# power.net
KiCad netlist of a schematic drawn in Altium Designer
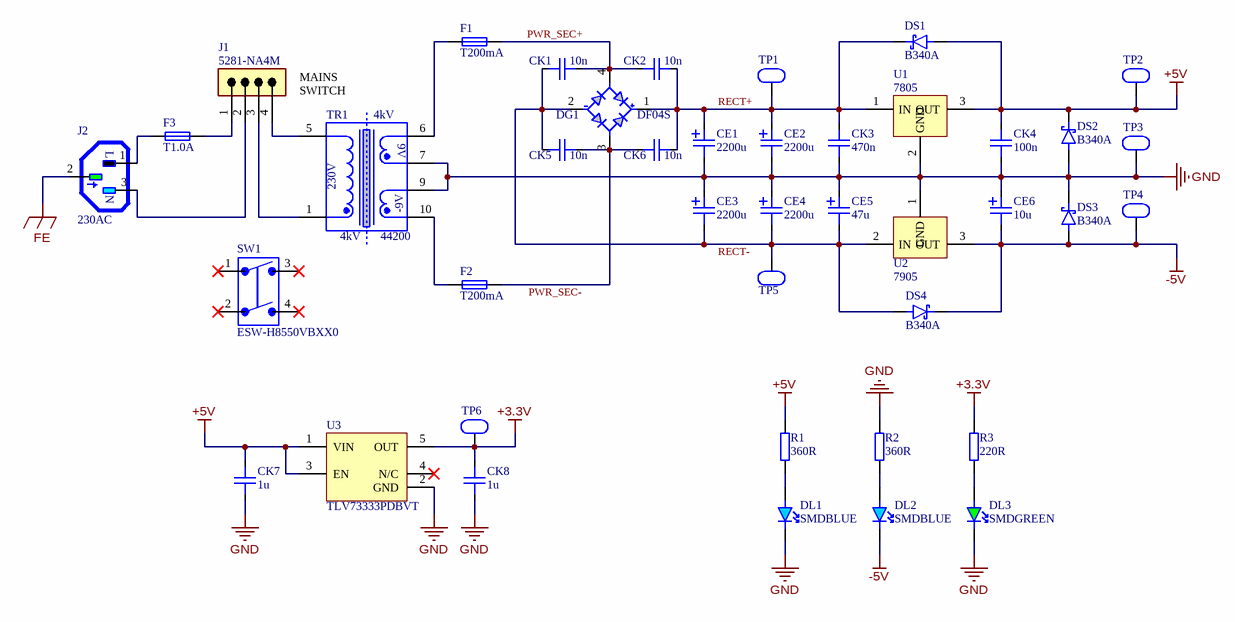
[diagram p0: power.SchDoc]

(export (version "E")
  (design (tool "Eeschema 10.0.6"))
  (components
    (comp (ref "CE1")
      (value "2200u")
      (footprint "ECE_16x31.5_RM7.5")
      (description "C; 2200u; 35V; 20%; Aluminum Electrolytic; ??;")
      (fields (field (name "MANUFACTURER") "SU'SCON: SL035M222J26SR;;SU'SCON: SL035M222J26TKKKS00R"))
      (libsource (lib "altium_sql") (part "CE"))
    )
    (comp (ref "CE2")
      (value "2200u")
      (footprint "ECE_16x31.5_RM7.5")
      (description "C; 2200u; 35V; 20%; Aluminum Electrolytic; ??;")
      (fields (field (name "MANUFACTURER") "SU'SCON: SL035M222J26SR;;SU'SCON: SL035M222J26TKKKS00R"))
      (libsource (lib "altium_sql") (part "CE"))
    )
    (comp (ref "CE3")
      (value "2200u")
      (footprint "ECE_16x31.5_RM7.5")
      (description "C; 2200u; 35V; 20%; Aluminum Electrolytic; ??;")
      (fields (field (name "MANUFACTURER") "SU'SCON: SL035M222J26SR;;SU'SCON: SL035M222J26TKKKS00R"))
      (libsource (lib "altium_sql") (part "CE"))
    )
    (comp (ref "CE4")
      (value "2200u")
      (footprint "ECE_16x31.5_RM7.5")
      (description "C; 2200u; 35V; 20%; Aluminum Electrolytic; ??;")
      (fields (field (name "MANUFACTURER") "SU'SCON: SL035M222J26SR;;SU'SCON: SL035M222J26TKKKS00R"))
      (libsource (lib "altium_sql") (part "CE"))
    )
    (comp (ref "CE5")
      (value "47u")
      (footprint "CAPAE6.8X6.8(D_SIZE)")
      (description "C; 47u; 35V; 20%; Aluminum Electrolytic; ??;")
      (fields (field (name "MANUFACTURER") "Surge, MPN: SVZ21V470M0605V1"))
      (libsource (lib "altium_sql") (part "CE"))
    )
    (comp (ref "CE6")
      (value "10u")
      (footprint "CAPAE5.5X5.5(C_SIZE)")
      (description "C; 10u; 35V; 20%; Aluminum Electrolytic; ??;")
      (fields (field (name "MANUFACTURER") "SAMWHA: SC1V106M05005VR259;;SAMWHA: SC1V106M05005VR289"))
      (libsource (lib "altium_sql") (part "CE"))
    )
    (comp (ref "CK1")
      (value "10n")
      (footprint "CAPC1608X09N(SMC0603)")
      (description "C; 10n; 50V; 5%; NP0/C0G; ??;")
      (fields (field (name "MANUFACTURER") "TDK: C1608C0G1H103J080AA"))
      (libsource (lib "altium_sql") (part "CK"))
    )
    (comp (ref "CK2")
      (value "10n")
      (footprint "CAPC1608X09N(SMC0603)")
      (description "C; 10n; 50V; 5%; NP0/C0G; ??;")
      (fields (field (name "MANUFACTURER") "TDK: C1608C0G1H103J080AA"))
      (libsource (lib "altium_sql") (part "CK"))
    )
    (comp (ref "CK3")
      (value "470n")
      (footprint "CAPC1608X09N(SMC0603)")
      (description "C; 470n; 50V; 10%; X7R; ??;")
      (fields
        (field (name "MANUFACTURER") "TDK: C1608X7R1H474KT-S;;TDK: C1608X7R1H474KT000E;;TDK: C1608X7R1H474K080AC")
      )
      (libsource (lib "altium_sql") (part "CK"))
    )
    (comp (ref "CK4")
      (value "100n")
      (footprint "CAPC1608X09N(SMC0603)")
      (description "C; 100n; 100V; 10%; X7R; ??;")
      (fields
        (field (name "MANUFACTURER") "Murata Electronics: GRM188R72A104KA35D;;Yageo: CC0603KRX7R0BB104")
      )
      (libsource (lib "altium_sql") (part "CK"))
    )
    (comp (ref "CK5")
      (value "10n")
      (footprint "CAPC1608X09N(SMC0603)")
      (description "C; 10n; 50V; 5%; NP0/C0G; ??;")
      (fields (field (name "MANUFACTURER") "TDK: C1608C0G1H103J080AA"))
      (libsource (lib "altium_sql") (part "CK"))
    )
    (comp (ref "CK6")
      (value "10n")
      (footprint "CAPC1608X09N(SMC0603)")
      (description "C; 10n; 50V; 5%; NP0/C0G; ??;")
      (fields (field (name "MANUFACTURER") "TDK: C1608C0G1H103J080AA"))
      (libsource (lib "altium_sql") (part "CK"))
    )
    (comp (ref "CK7")
      (value "1u")
      (footprint "CAPC1608X09N(SMC0603)")
      (description "C; 1u; 50V; 10%; X5R; ??;")
      (libsource (lib "altium_sql") (part "CK"))
    )
    (comp (ref "CK8")
      (value "1u")
      (footprint "CAPC1608X09N(SMC0603)")
      (description "C; 1u; 50V; 10%; X5R; ??;")
      (libsource (lib "altium_sql") (part "CK"))
    )
    (comp (ref "DG1")
      (value "DF04S")
      (footprint "DIP300RM5.08_SMD")
      (description "D; Bridge; 400V; 1A; 1x;")
      (libsource (lib "altium_sql") (part "EDG+DF04SXX0"))
    )
    (comp (ref "DL1")
      (value "SMDBLUE")
      (footprint "DIOC2012X12N(SMLED0805)B")
      (description "Ind; Light; Blue;")
      (fields (field (name "MANUFACTURER") "MULTICOMP: OVS-0803"))
      (libsource (lib "altium_sql") (part "DL_B"))
    )
    (comp (ref "DL2")
      (value "SMDBLUE")
      (footprint "DIOC2012X12N(SMLED0805)B")
      (description "Ind; Light; Blue;")
      (fields (field (name "MANUFACTURER") "MULTICOMP: OVS-0803"))
      (libsource (lib "altium_sql") (part "DL_B"))
    )
    (comp (ref "DL3")
      (value "SMDGREEN")
      (footprint "DIOC2012X12N(SMLED0805)G")
      (description "Ind; Light; Green;")
      (fields (field (name "MANUFACTURER") "HEBEI: 0805KGCT;;BRIGHTLED: BL-HGE35A-AV-TRB"))
      (libsource (lib "altium_sql") (part "DL_G"))
    )
    (comp (ref "DS1")
      (value "B340A")
      (footprint "DIOM5127X23N(SMA)")
      (description "D; Schottky; 40V; 3A; 1x;")
      (fields
        (field (name "MANUFACTURER") "DIODES INC: B340A-13-F;;ONS: MBRA340T3G;;VISHAY: SSA34;;BOURNS: B340LF;;MCC: SK34A-LTP")
      )
      (libsource (lib "altium_sql") (part "DS"))
    )
    (comp (ref "DS2")
      (value "B340A")
      (footprint "DIOM5127X23N(SMA)")
      (description "D; Schottky; 40V; 3A; 1x;")
      (fields
        (field (name "MANUFACTURER") "DIODES INC: B340A-13-F;;ONS: MBRA340T3G;;VISHAY: SSA34;;BOURNS: B340LF;;MCC: SK34A-LTP")
      )
      (libsource (lib "altium_sql") (part "DS"))
    )
    (comp (ref "DS3")
      (value "B340A")
      (footprint "DIOM5127X23N(SMA)")
      (description "D; Schottky; 40V; 3A; 1x;")
      (fields
        (field (name "MANUFACTURER") "DIODES INC: B340A-13-F;;ONS: MBRA340T3G;;VISHAY: SSA34;;BOURNS: B340LF;;MCC: SK34A-LTP")
      )
      (libsource (lib "altium_sql") (part "DS"))
    )
    (comp (ref "DS4")
      (value "B340A")
      (footprint "DIOM5127X23N(SMA)")
      (description "D; Schottky; 40V; 3A; 1x;")
      (fields
        (field (name "MANUFACTURER") "DIODES INC: B340A-13-F;;ONS: MBRA340T3G;;VISHAY: SSA34;;BOURNS: B340LF;;MCC: SK34A-LTP")
      )
      (libsource (lib "altium_sql") (part "DS"))
    )
    (comp (ref "F1")
      (value "T200mA")
      (footprint "FUSE-C8.5")
      (description "CP; Current [A]; 0.2; R:No; 1x;")
      (fields (field (name "MANUFACTURER") "SCHURTER: MST250 0034.6608;;SCHURTER: MST250 0034.6708"))
      (libsource (lib "altium_sql") (part "FUSE_PCB"))
    )
    (comp (ref "F2")
      (value "T200mA")
      (footprint "FUSE-C8.5")
      (description "CP; Current [A]; 0.2; R:No; 1x;")
      (fields (field (name "MANUFACTURER") "SCHURTER: MST250 0034.6608;;SCHURTER: MST250 0034.6708"))
      (libsource (lib "altium_sql") (part "FUSE_PCB"))
    )
    (comp (ref "F3")
      (value "T1.0A")
      (footprint "FUSE-C8.5")
      (description "CP; Current [A]; 1; R:No; 1x;")
      (fields (field (name "MANUFACTURER") "SCHURTER: 34,6615"))
      (libsource (lib "altium_sql") (part "FUSE_PCB"))
    )
    (comp (ref "J1")
      (value "5281-NA4M")
      (footprint "4P-NA-5.08")
      (description "Con; Wire to board RM5.04; 4x; PCB; Straight; 250V; 7A; Male; Tin; ??;")
      (fields
        (field (name "MANUFACTURER") "HSUAN MAO: W4508-04PSYTW0R;;HSM: W4508-04PSYTW0R;;MOLEX: 10-32-1041")
      )
      (libsource (lib "altium_sql") (part "EJ-5281-NA4MX0"))
    )
    (comp (ref "J2")
      (value "230AC")
      (footprint "SCHURTER_GSP1.8501.1")
      (description "Con; AC plug; 1x; PCB; ??; 250V; 10A; Male; Tin; ??;")
      (fields (field (name "MANUFACTURER") "SCHURTER: GSP1.8501.1"))
      (libsource (lib "altium_sql") (part "EJ-GSP1SC1"))
    )
    (comp (ref "R1")
      (value "360R")
      (footprint "RESC1608X06N(SMR0603)")
      (description "R; 470R; 0.1W; 1%; 75V; Thick Film; ±100ppm/K; 1x;")
      (fields (field (name "MANUFACTURER") "Yageo: RC0603FR-07470RL;;Panasonic: ERJ3EKF4700V"))
      (libsource (lib "altium_sql") (part "R"))
    )
    (comp (ref "R2")
      (value "360R")
      (footprint "RESC1608X06N(SMR0603)")
      (description "R; 470R; 0.1W; 1%; 75V; Thick Film; ±100ppm/K; 1x;")
      (fields (field (name "MANUFACTURER") "Yageo: RC0603FR-07470RL;;Panasonic: ERJ3EKF4700V"))
      (libsource (lib "altium_sql") (part "R"))
    )
    (comp (ref "R3")
      (value "220R")
      (footprint "RESC1608X06N(SMR0603)")
      (description "R; 470R; 0.1W; 1%; 75V; Thick Film; ±100ppm/K; 1x;")
      (fields (field (name "MANUFACTURER") "Yageo: RC0603FR-07470RL;;Panasonic: ERJ3EKF4700V"))
      (libsource (lib "altium_sql") (part "R"))
    )
    (comp (ref "SW1")
      (value "ESW-H8550VBXX0")
      (description "MSw; DPST; Panel; 2x; DC:??V; DC:??A; AC:250V; AC:9A; CV:??V; Switch;")
      (fields (field (name "MANUFACTURER") "SWITRONIC: R19-20.BBBT;;SWITRONIC: R19-20.BBBT+-G"))
      (libsource (lib "altium_sql") (part "ESW-H8550VBXX0"))
    )
    (comp (ref "TP1")
      (value "Test Point")
      (footprint "SMD_Testpoint_Onelayer")
      (description "Con; Test Point; 1x; PCB; ??; ??V; ??A; ??; Tin; Contact;")
      (fields (field (name "MANUFACTURER") "Harwin: S1751-46R") (field (name "CONNECTOR_PART") "Contact"))
      (libsource (lib "altium_sql") (part "EJ+TESTPOINTXX0"))
    )
    (comp (ref "TP2")
      (value "Test Point")
      (footprint "SMD_Testpoint_Onelayer")
      (description "Con; Test Point; 1x; PCB; ??; ??V; ??A; ??; Tin; Contact;")
      (fields (field (name "MANUFACTURER") "Harwin: S1751-46R") (field (name "CONNECTOR_PART") "Contact"))
      (libsource (lib "altium_sql") (part "EJ+TESTPOINTXX0"))
    )
    (comp (ref "TP3")
      (value "Test Point")
      (footprint "SMD_Testpoint_Onelayer")
      (description "Con; Test Point; 1x; PCB; ??; ??V; ??A; ??; Tin; Contact;")
      (fields (field (name "MANUFACTURER") "Harwin: S1751-46R") (field (name "CONNECTOR_PART") "Contact"))
      (libsource (lib "altium_sql") (part "EJ+TESTPOINTXX0"))
    )
    (comp (ref "TP4")
      (value "Test Point")
      (footprint "SMD_Testpoint_Onelayer")
      (description "Con; Test Point; 1x; PCB; ??; ??V; ??A; ??; Tin; Contact;")
      (fields (field (name "MANUFACTURER") "Harwin: S1751-46R") (field (name "CONNECTOR_PART") "Contact"))
      (libsource (lib "altium_sql") (part "EJ+TESTPOINTXX0"))
    )
    (comp (ref "TP5")
      (value "Test Point")
      (footprint "SMD_Testpoint_Onelayer")
      (description "Con; Test Point; 1x; PCB; ??; ??V; ??A; ??; Tin; Contact;")
      (fields (field (name "MANUFACTURER") "Harwin: S1751-46R") (field (name "CONNECTOR_PART") "Contact"))
      (libsource (lib "altium_sql") (part "EJ+TESTPOINTXX0"))
    )
    (comp (ref "TP6")
      (value "Test Point")
      (footprint "SMD_Testpoint_Onelayer")
      (description "Con; Test Point; 1x; PCB; ??; ??V; ??A; ??; Tin; Contact;")
      (fields (field (name "MANUFACTURER") "Harwin: S1751-46R") (field (name "CONNECTOR_PART") "Contact"))
      (libsource (lib "altium_sql") (part "EJ+TESTPOINTXX0"))
    )
    (comp (ref "TR1")
      (value "44200")
      (footprint "44200")
      (description "Transformer 230V/2x9V, 2x178mA")
      (libsource (lib "custom-footprints") (part "44200"))
    )
    (comp (ref "U1")
      (value "7805")
      (footprint "DPAK254P1544X483-3N(D2PAK)")
      (description "Fixed, Three Terminal Pos  Regulator 5V/1A in D2PAK")
      (libsource (lib "custom-footprints") (part "L7805AC"))
    )
    (comp (ref "U2")
      (value "7905")
      (footprint "DPAK254P1544X483-3N(D2PAK)")
      (description "Fixed, Three Terminal Pos  Regulator -5V/1A in D2PAK")
      (libsource (lib "custom-footprints") (part "L7905AC"))
    )
    (comp (ref "U3")
      (value "TLV73333PDBVT")
      (footprint "SOT95P280X145-5N(SOT23-5)")
      (description "IC; Linear Regulator/Reference; ??V; 5.5V; 1x;")
      (fields (field (name "MANUFACTURER") "Texas Instruments: TLV73333PDBVT"))
      (libsource (lib "altium_sql") (part "EU+NCV8702SN18XX0"))
    )
  )
  (nets
    (net (code "1") (name "+3.3V") (class "Default")
      (node (ref "CK8") (pin "1") (pinfunction "1_1") (pintype "passive"))
      (node (ref "R3") (pin "2") (pinfunction "2_2") (pintype "passive"))
      (node (ref "TP6") (pin "1") (pintype "passive"))
      (node (ref "U3") (pin "5") (pinfunction "OUT_5") (pintype "power_in"))
    )
    (net (code "2") (name "+5V") (class "Default")
      (node (ref "CK4") (pin "1") (pinfunction "1_1") (pintype "passive"))
      (node (ref "CK7") (pin "1") (pinfunction "1_1") (pintype "passive"))
      (node (ref "DS1") (pin "2") (pinfunction "A_2") (pintype "passive"))
      (node (ref "DS2") (pin "1") (pinfunction "C_1") (pintype "passive"))
      (node (ref "R1") (pin "2") (pinfunction "2_2") (pintype "passive"))
      (node (ref "TP2") (pin "1") (pintype "passive"))
      (node (ref "U1") (pin "3") (pinfunction "OUT_3") (pintype "passive"))
      (node (ref "U3") (pin "1") (pinfunction "VIN_1") (pintype "power_in"))
      (node (ref "U3") (pin "3") (pinfunction "EN_3") (pintype "passive"))
    )
    (net (code "3") (name "-5V") (class "Default")
      (node (ref "CE6") (pin "2") (pinfunction "2_2") (pintype "passive"))
      (node (ref "DL2") (pin "1") (pinfunction "C_1") (pintype "passive"))
      (node (ref "DS3") (pin "2") (pinfunction "A_2") (pintype "passive"))
      (node (ref "DS4") (pin "1") (pinfunction "C_1") (pintype "passive"))
      (node (ref "TP4") (pin "1") (pintype "passive"))
      (node (ref "U2") (pin "3") (pinfunction "OUT_3") (pintype "passive"))
    )
    (net (code "4") (name "/PWR_SEC+") (class "Default")
      (node (ref "CK1") (pin "2") (pinfunction "2_2") (pintype "passive"))
      (node (ref "CK2") (pin "1") (pinfunction "1_1") (pintype "passive"))
      (node (ref "DG1") (pin "4") (pinfunction "AC_4") (pintype "passive"))
      (node (ref "F1") (pin "2") (pintype "passive"))
    )
    (net (code "5") (name "/PWR_SEC-") (class "Default")
      (node (ref "CK5") (pin "2") (pinfunction "2_2") (pintype "passive"))
      (node (ref "CK6") (pin "1") (pinfunction "1_1") (pintype "passive"))
      (node (ref "DG1") (pin "3") (pinfunction "AC_3") (pintype "passive"))
      (node (ref "F2") (pin "2") (pintype "passive"))
    )
    (net (code "6") (name "/RECT+") (class "Default")
      (node (ref "CE1") (pin "1") (pinfunction "1_1") (pintype "passive"))
      (node (ref "CE2") (pin "1") (pinfunction "1_1") (pintype "passive"))
      (node (ref "CK2") (pin "2") (pinfunction "2_2") (pintype "passive"))
      (node (ref "CK3") (pin "1") (pinfunction "1_1") (pintype "passive"))
      (node (ref "CK6") (pin "2") (pinfunction "2_2") (pintype "passive"))
      (node (ref "DG1") (pin "1") (pinfunction "+_1") (pintype "passive"))
      (node (ref "DS1") (pin "1") (pinfunction "C_1") (pintype "passive"))
      (node (ref "TP1") (pin "1") (pintype "passive"))
      (node (ref "U1") (pin "1") (pinfunction "IN_1") (pintype "passive"))
    )
    (net (code "7") (name "/RECT-") (class "Default")
      (node (ref "CE3") (pin "2") (pinfunction "2_2") (pintype "passive"))
      (node (ref "CE4") (pin "2") (pinfunction "2_2") (pintype "passive"))
      (node (ref "CE5") (pin "2") (pinfunction "2_2") (pintype "passive"))
      (node (ref "CK1") (pin "1") (pinfunction "1_1") (pintype "passive"))
      (node (ref "CK5") (pin "1") (pinfunction "1_1") (pintype "passive"))
      (node (ref "DG1") (pin "2") (pinfunction "-_2") (pintype "passive"))
      (node (ref "DS4") (pin "2") (pinfunction "A_2") (pintype "passive"))
      (node (ref "TP5") (pin "1") (pintype "passive"))
      (node (ref "U2") (pin "2") (pinfunction "IN_2") (pintype "passive"))
    )
    (net (code "8") (name "FE") (class "Default") (node (ref "J2") (pin "2") (pintype "passive")))
    (net (code "9") (name "GND") (class "Default")
      (node (ref "CE1") (pin "2") (pinfunction "2_2") (pintype "passive"))
      (node (ref "CE2") (pin "2") (pinfunction "2_2") (pintype "passive"))
      (node (ref "CE3") (pin "1") (pinfunction "1_1") (pintype "passive"))
      (node (ref "CE4") (pin "1") (pinfunction "1_1") (pintype "passive"))
      (node (ref "CE5") (pin "1") (pinfunction "1_1") (pintype "passive"))
      (node (ref "CE6") (pin "1") (pinfunction "1_1") (pintype "passive"))
      (node (ref "CK3") (pin "2") (pinfunction "2_2") (pintype "passive"))
      (node (ref "CK4") (pin "2") (pinfunction "2_2") (pintype "passive"))
      (node (ref "CK7") (pin "2") (pinfunction "2_2") (pintype "passive"))
      (node (ref "CK8") (pin "2") (pinfunction "2_2") (pintype "passive"))
      (node (ref "DL1") (pin "1") (pinfunction "C_1") (pintype "passive"))
      (node (ref "DL3") (pin "1") (pinfunction "C_1") (pintype "passive"))
      (node (ref "DS2") (pin "2") (pinfunction "A_2") (pintype "passive"))
      (node (ref "DS3") (pin "1") (pinfunction "C_1") (pintype "passive"))
      (node (ref "R2") (pin "2") (pinfunction "2_2") (pintype "passive"))
      (node (ref "TP3") (pin "1") (pintype "passive"))
      (node (ref "TR1") (pin "7") (pintype "power_in"))
      (node (ref "TR1") (pin "9") (pintype "power_in"))
      (node (ref "U1") (pin "2") (pinfunction "GND_2") (pintype "passive"))
      (node (ref "U2") (pin "1") (pinfunction "GND_1") (pintype "passive"))
      (node (ref "U3") (pin "2") (pinfunction "GND_2") (pintype "power_in"))
    )
    (net (code "10") (name "Net-(DL1-A)") (class "Default")
      (node (ref "DL1") (pin "2") (pinfunction "A_2") (pintype "passive"))
      (node (ref "R1") (pin "1") (pinfunction "1_1") (pintype "passive"))
    )
    (net (code "11") (name "Net-(DL2-A)") (class "Default")
      (node (ref "DL2") (pin "2") (pinfunction "A_2") (pintype "passive"))
      (node (ref "R2") (pin "1") (pinfunction "1_1") (pintype "passive"))
    )
    (net (code "12") (name "Net-(DL3-A)") (class "Default")
      (node (ref "DL3") (pin "2") (pinfunction "A_2") (pintype "passive"))
      (node (ref "R3") (pin "1") (pinfunction "1_1") (pintype "passive"))
    )
    (net (code "13") (name "Net-(F1-Pad1)") (class "Default")
      (node (ref "F1") (pin "1") (pintype "passive"))
      (node (ref "TR1") (pin "6") (pintype "power_in"))
    )
    (net (code "14") (name "Net-(F2-Pad1)") (class "Default")
      (node (ref "F2") (pin "1") (pintype "passive"))
      (node (ref "TR1") (pin "10") (pintype "power_in"))
    )
    (net (code "15") (name "Net-(F3-Pad1)") (class "Default")
      (node (ref "F3") (pin "1") (pintype "passive"))
      (node (ref "J2") (pin "1") (pintype "passive"))
    )
    (net (code "16") (name "Net-(F3-Pad2)") (class "Default")
      (node (ref "F3") (pin "2") (pintype "passive"))
      (node (ref "J1") (pin "1") (pinfunction "1_1") (pintype "passive"))
    )
    (net (code "17") (name "Net-(J1-4)") (class "Default")
      (node (ref "J1") (pin "3") (pinfunction "4_3") (pintype "passive"))
      (node (ref "TR1") (pin "1") (pintype "power_in"))
    )
    (net (code "18") (name "Net-(J1-6)") (class "Default")
      (node (ref "J1") (pin "4") (pinfunction "6_4") (pintype "passive"))
      (node (ref "TR1") (pin "5") (pintype "power_in"))
    )
    (net (code "19") (name "Net-(J1-Pad2)") (class "Default")
      (node (ref "J1") (pin "2") (pinfunction "2_2") (pintype "passive"))
      (node (ref "J2") (pin "3") (pintype "passive"))
    )
    (net (code "20") (name "unconnected-(SW1-Pad1)") (class "Default")
      (node (ref "SW1") (pin "1") (pintype "passive+no_connect"))
    )
    (net (code "21") (name "unconnected-(SW1-Pad2)") (class "Default")
      (node (ref "SW1") (pin "2") (pintype "passive+no_connect"))
    )
    (net (code "22") (name "unconnected-(SW1-Pad3)") (class "Default")
      (node (ref "SW1") (pin "3") (pintype "passive+no_connect"))
    )
    (net (code "23") (name "unconnected-(SW1-Pad4)") (class "Default")
      (node (ref "SW1") (pin "4") (pintype "passive+no_connect"))
    )
    (net (code "24") (name "unconnected-(U3-N{slash}C-Pad4)") (class "Default")
      (node (ref "U3") (pin "4") (pinfunction "N/C_4") (pintype "power_in+no_connect"))
    )
  )
)
